# SCH_USB-Hub.net
KiCad netlist of a schematic drawn in EasyEDA
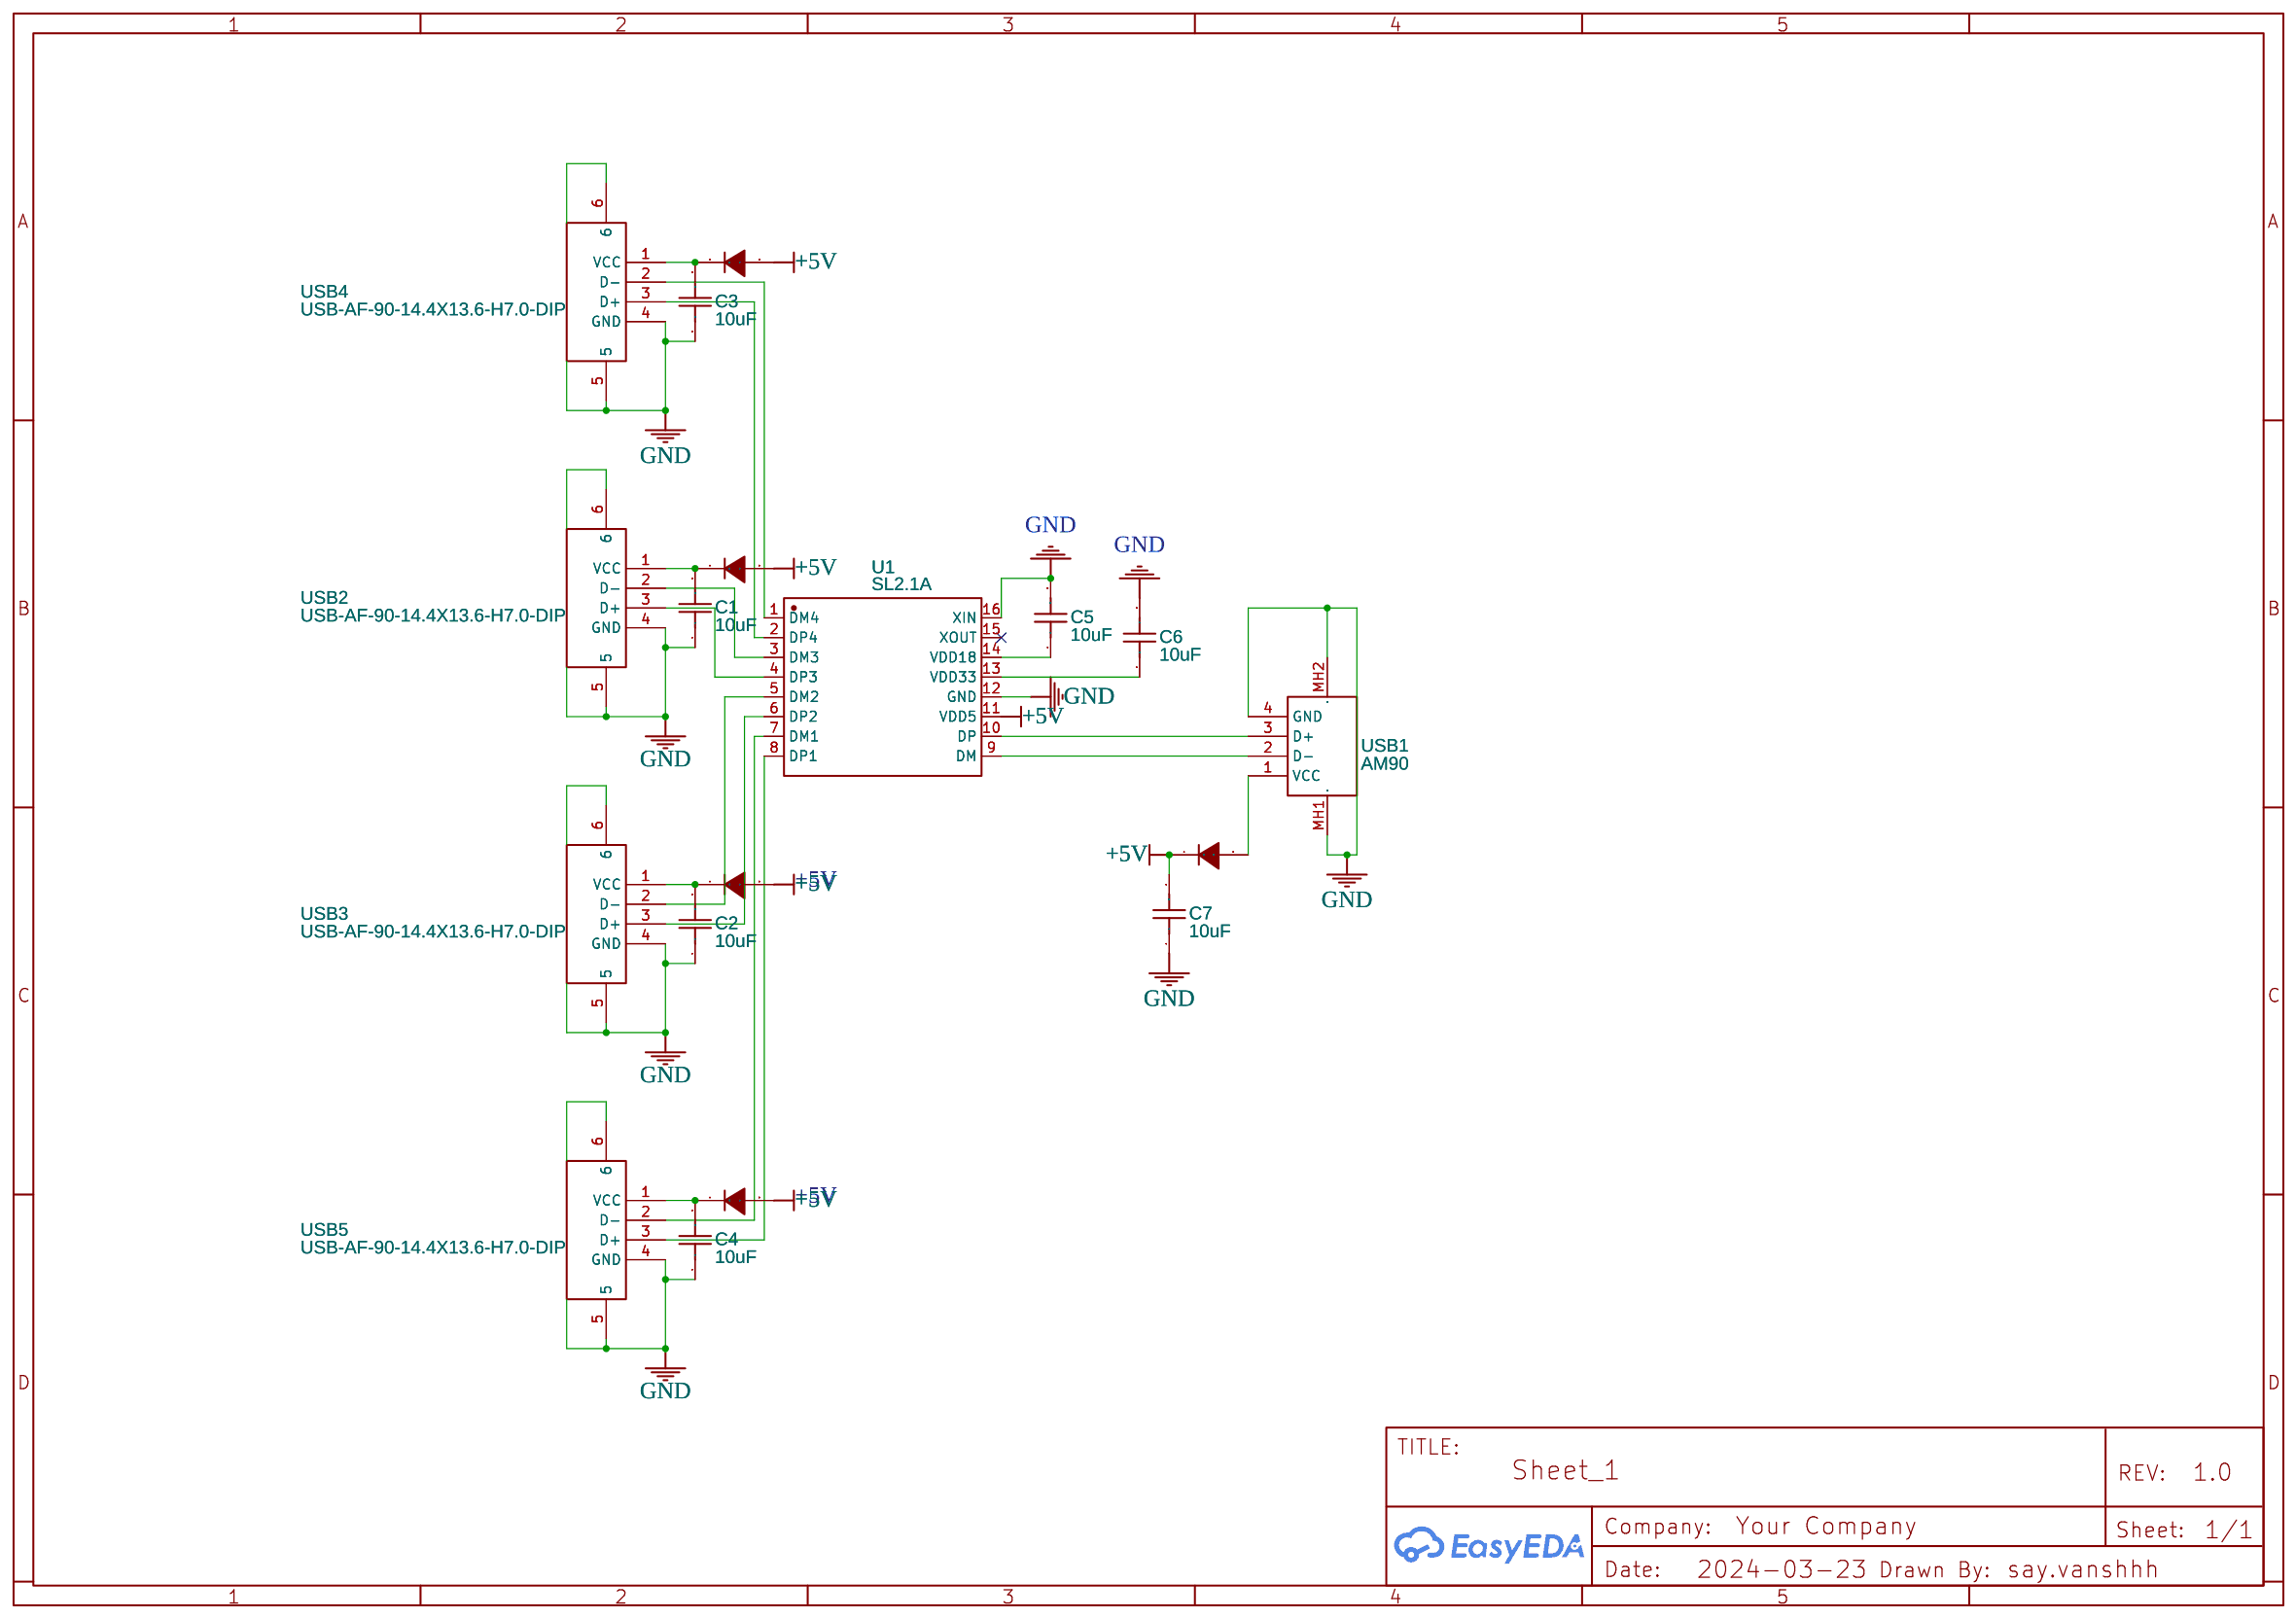
[diagram p0: schematic sheet]

(export (version "E")
  (design (tool "Eeschema 10.0.6"))
  (components
    (comp (ref "C1")
      (value "10uF")
      (fields
        (field (name "Manufacturer Part") "CL10A106KP8NNNC")
        (field (name "Manufacturer") "SAMSUNG(三星)")
      )
      (libsource (lib "") (part "CL10A106KP8NNNC"))
    )
    (comp (ref "C2")
      (value "10uF")
      (fields
        (field (name "Manufacturer Part") "CL10A106KP8NNNC")
        (field (name "Manufacturer") "SAMSUNG(三星)")
      )
      (libsource (lib "") (part "CL10A106KP8NNNC"))
    )
    (comp (ref "C3")
      (value "10uF")
      (fields
        (field (name "Manufacturer Part") "CL10A106KP8NNNC")
        (field (name "Manufacturer") "SAMSUNG(三星)")
      )
      (libsource (lib "") (part "CL10A106KP8NNNC"))
    )
    (comp (ref "C4")
      (value "10uF")
      (fields
        (field (name "Manufacturer Part") "CL10A106KP8NNNC")
        (field (name "Manufacturer") "SAMSUNG(三星)")
      )
      (libsource (lib "") (part "CL10A106KP8NNNC"))
    )
    (comp (ref "C5")
      (value "10uF")
      (fields
        (field (name "Manufacturer Part") "CL10A106KP8NNNC")
        (field (name "Manufacturer") "SAMSUNG(三星)")
      )
      (libsource (lib "") (part "CL10A106KP8NNNC"))
    )
    (comp (ref "C6")
      (value "10uF")
      (fields
        (field (name "Manufacturer Part") "CL10A106KP8NNNC")
        (field (name "Manufacturer") "SAMSUNG(三星)")
      )
      (libsource (lib "") (part "CL10A106KP8NNNC"))
    )
    (comp (ref "C7")
      (value "10uF")
      (fields
        (field (name "Manufacturer Part") "CL10A106KP8NNNC")
        (field (name "Manufacturer") "SAMSUNG(三星)")
      )
      (libsource (lib "") (part "CL10A106KP8NNNC"))
    )
    (comp (ref "D1")
      (value "NSR0320MW2T1G")
      (fields (field (name "Manufacturer") "onsemi(安森美)"))
      (libsource (lib "") (part "NSR0320MW2T1G"))
    )
    (comp (ref "D2")
      (value "NSR0320MW2T1G")
      (fields (field (name "Manufacturer") "onsemi(安森美)"))
      (libsource (lib "") (part "NSR0320MW2T1G"))
    )
    (comp (ref "D3")
      (value "NSR0320MW2T1G")
      (fields (field (name "Manufacturer") "onsemi(安森美)"))
      (libsource (lib "") (part "NSR0320MW2T1G"))
    )
    (comp (ref "D4")
      (value "NSR0320MW2T1G")
      (fields (field (name "Manufacturer") "onsemi(安森美)"))
      (libsource (lib "") (part "NSR0320MW2T1G"))
    )
    (comp (ref "D5")
      (value "NSR0320MW2T1G")
      (fields (field (name "Manufacturer") "onsemi(安森美)"))
      (libsource (lib "") (part "NSR0320MW2T1G"))
    )
    (comp (ref "U1")
      (value "SL2.1A")
      (fields (field (name "Manufacturer") "CoreChips(和芯润德)"))
      (libsource (lib "") (part "SL2.1A"))
    )
    (comp (ref "USB1")
      (value "AM90")
      (fields (field (name "Manufacturer") "SHOU HAN(首韩)"))
      (libsource (lib "") (part "AM90"))
    )
    (comp (ref "USB2")
      (value "USB-AF-90-14.4X13.6-H7.0-DIP")
      (fields (field (name "Manufacturer Part") "903-131A1011D10100") (field (name "Manufacturer") "精拓金"))
      (libsource (lib "") (part "USB-AF-90-14.4X13.6-H7.0-DIP"))
    )
    (comp (ref "USB3")
      (value "USB-AF-90-14.4X13.6-H7.0-DIP")
      (fields (field (name "Manufacturer Part") "903-131A1011D10100") (field (name "Manufacturer") "精拓金"))
      (libsource (lib "") (part "USB-AF-90-14.4X13.6-H7.0-DIP"))
    )
    (comp (ref "USB4")
      (value "USB-AF-90-14.4X13.6-H7.0-DIP")
      (fields (field (name "Manufacturer Part") "903-131A1011D10100") (field (name "Manufacturer") "精拓金"))
      (libsource (lib "") (part "USB-AF-90-14.4X13.6-H7.0-DIP"))
    )
    (comp (ref "USB5")
      (value "USB-AF-90-14.4X13.6-H7.0-DIP")
      (fields (field (name "Manufacturer Part") "903-131A1011D10100") (field (name "Manufacturer") "精拓金"))
      (libsource (lib "") (part "USB-AF-90-14.4X13.6-H7.0-DIP"))
    )
  )
  (nets
    (net (code "1") (name "+5V") (class "Default")
      (node (ref "C7") (pin "2") (pinfunction "2_2") (pintype "unspecified"))
      (node (ref "D1") (pin "2") (pinfunction "A_2") (pintype "unspecified"))
      (node (ref "D2") (pin "2") (pinfunction "A_2") (pintype "unspecified"))
      (node (ref "D3") (pin "2") (pinfunction "A_2") (pintype "unspecified"))
      (node (ref "D4") (pin "2") (pinfunction "A_2") (pintype "unspecified"))
      (node (ref "D5") (pin "1") (pinfunction "C_1") (pintype "unspecified"))
      (node (ref "U1") (pin "11") (pinfunction "VDD5_11") (pintype "unspecified"))
    )
    (net (code "2") (name "GND") (class "Default")
      (node (ref "C1") (pin "1") (pinfunction "1_1") (pintype "unspecified"))
      (node (ref "C2") (pin "1") (pinfunction "1_1") (pintype "unspecified"))
      (node (ref "C3") (pin "1") (pinfunction "1_1") (pintype "unspecified"))
      (node (ref "C4") (pin "1") (pinfunction "1_1") (pintype "unspecified"))
      (node (ref "C5") (pin "2") (pinfunction "2_2") (pintype "unspecified"))
      (node (ref "C6") (pin "2") (pinfunction "2_2") (pintype "unspecified"))
      (node (ref "C7") (pin "1") (pinfunction "1_1") (pintype "unspecified"))
      (node (ref "U1") (pin "12") (pinfunction "GND_12") (pintype "unspecified"))
      (node (ref "U1") (pin "16") (pinfunction "XIN_16") (pintype "unspecified"))
      (node (ref "USB1") (pin "4") (pinfunction "GND_4") (pintype "input"))
      (node (ref "USB1") (pin "MH1") (pinfunction "MH1_MH1") (pintype "unspecified"))
      (node (ref "USB1") (pin "MH2") (pinfunction "MH2_MH2") (pintype "unspecified"))
      (node (ref "USB2") (pin "4") (pinfunction "GND_4") (pintype "unspecified"))
      (node (ref "USB2") (pin "5") (pinfunction "5_5") (pintype "unspecified"))
      (node (ref "USB3") (pin "4") (pinfunction "GND_4") (pintype "unspecified"))
      (node (ref "USB3") (pin "5") (pinfunction "5_5") (pintype "unspecified"))
      (node (ref "USB4") (pin "4") (pinfunction "GND_4") (pintype "unspecified"))
      (node (ref "USB4") (pin "5") (pinfunction "5_5") (pintype "unspecified"))
      (node (ref "USB5") (pin "4") (pinfunction "GND_4") (pintype "unspecified"))
      (node (ref "USB5") (pin "5") (pinfunction "5_5") (pintype "unspecified"))
    )
    (net (code "3") (name "Net-(D1-C)") (class "Default")
      (node (ref "C1") (pin "2") (pinfunction "2_2") (pintype "unspecified"))
      (node (ref "D1") (pin "1") (pinfunction "C_1") (pintype "unspecified"))
      (node (ref "USB2") (pin "1") (pinfunction "VCC_1") (pintype "unspecified"))
    )
    (net (code "4") (name "Net-(D2-C)") (class "Default")
      (node (ref "C3") (pin "2") (pinfunction "2_2") (pintype "unspecified"))
      (node (ref "D2") (pin "1") (pinfunction "C_1") (pintype "unspecified"))
      (node (ref "USB4") (pin "1") (pinfunction "VCC_1") (pintype "unspecified"))
    )
    (net (code "5") (name "Net-(D3-C)") (class "Default")
      (node (ref "C2") (pin "2") (pinfunction "2_2") (pintype "unspecified"))
      (node (ref "D3") (pin "1") (pinfunction "C_1") (pintype "unspecified"))
      (node (ref "USB3") (pin "1") (pinfunction "VCC_1") (pintype "unspecified"))
    )
    (net (code "6") (name "Net-(D4-C)") (class "Default")
      (node (ref "C4") (pin "2") (pinfunction "2_2") (pintype "unspecified"))
      (node (ref "D4") (pin "1") (pinfunction "C_1") (pintype "unspecified"))
      (node (ref "USB5") (pin "1") (pinfunction "VCC_1") (pintype "unspecified"))
    )
    (net (code "7") (name "Net-(D5-A)") (class "Default")
      (node (ref "D5") (pin "2") (pinfunction "A_2") (pintype "unspecified"))
      (node (ref "USB1") (pin "1") (pinfunction "VCC_1") (pintype "input"))
    )
    (net (code "8") (name "Net-(U1-DM)") (class "Default")
      (node (ref "U1") (pin "9") (pinfunction "DM_9") (pintype "unspecified"))
      (node (ref "USB1") (pin "2") (pinfunction "D-_2") (pintype "input"))
    )
    (net (code "9") (name "Net-(U1-DM1)") (class "Default")
      (node (ref "U1") (pin "7") (pinfunction "DM1_7") (pintype "unspecified"))
      (node (ref "USB5") (pin "2") (pinfunction "D-_2") (pintype "unspecified"))
    )
    (net (code "10") (name "Net-(U1-DM2)") (class "Default")
      (node (ref "U1") (pin "5") (pinfunction "DM2_5") (pintype "unspecified"))
      (node (ref "USB3") (pin "2") (pinfunction "D-_2") (pintype "unspecified"))
    )
    (net (code "11") (name "Net-(U1-DM3)") (class "Default")
      (node (ref "U1") (pin "3") (pinfunction "DM3_3") (pintype "unspecified"))
      (node (ref "USB2") (pin "2") (pinfunction "D-_2") (pintype "unspecified"))
    )
    (net (code "12") (name "Net-(U1-DM4)") (class "Default")
      (node (ref "U1") (pin "1") (pinfunction "DM4_1") (pintype "unspecified"))
      (node (ref "USB4") (pin "2") (pinfunction "D-_2") (pintype "unspecified"))
    )
    (net (code "13") (name "Net-(U1-DP)") (class "Default")
      (node (ref "U1") (pin "10") (pinfunction "DP_10") (pintype "unspecified"))
      (node (ref "USB1") (pin "3") (pinfunction "D+_3") (pintype "input"))
    )
    (net (code "14") (name "Net-(U1-DP1)") (class "Default")
      (node (ref "U1") (pin "8") (pinfunction "DP1_8") (pintype "unspecified"))
      (node (ref "USB5") (pin "3") (pinfunction "D+_3") (pintype "unspecified"))
    )
    (net (code "15") (name "Net-(U1-DP2)") (class "Default")
      (node (ref "U1") (pin "6") (pinfunction "DP2_6") (pintype "unspecified"))
      (node (ref "USB3") (pin "3") (pinfunction "D+_3") (pintype "unspecified"))
    )
    (net (code "16") (name "Net-(U1-DP3)") (class "Default")
      (node (ref "U1") (pin "4") (pinfunction "DP3_4") (pintype "unspecified"))
      (node (ref "USB2") (pin "3") (pinfunction "D+_3") (pintype "unspecified"))
    )
    (net (code "17") (name "Net-(U1-DP4)") (class "Default")
      (node (ref "U1") (pin "2") (pinfunction "DP4_2") (pintype "unspecified"))
      (node (ref "USB4") (pin "3") (pinfunction "D+_3") (pintype "unspecified"))
    )
    (net (code "18") (name "Net-(U1-VDD18)") (class "Default")
      (node (ref "C5") (pin "1") (pinfunction "1_1") (pintype "unspecified"))
      (node (ref "U1") (pin "14") (pinfunction "VDD18_14") (pintype "unspecified"))
    )
    (net (code "19") (name "Net-(U1-VDD33)") (class "Default")
      (node (ref "C6") (pin "1") (pinfunction "1_1") (pintype "unspecified"))
      (node (ref "U1") (pin "13") (pinfunction "VDD33_13") (pintype "unspecified"))
    )
    (net (code "20") (name "unconnected-(U1-XOUT-Pad15)") (class "Default")
      (node (ref "U1") (pin "15") (pinfunction "XOUT_15") (pintype "unspecified+no_connect"))
    )
    (net (code "21") (name "unconnected-(USB2-Pad6)") (class "Default")
      (node (ref "USB2") (pin "6") (pinfunction "6_6") (pintype "unspecified"))
    )
    (net (code "22") (name "unconnected-(USB3-Pad6)") (class "Default")
      (node (ref "USB3") (pin "6") (pinfunction "6_6") (pintype "unspecified"))
    )
    (net (code "23") (name "unconnected-(USB4-Pad6)") (class "Default")
      (node (ref "USB4") (pin "6") (pinfunction "6_6") (pintype "unspecified"))
    )
    (net (code "24") (name "unconnected-(USB5-Pad6)") (class "Default")
      (node (ref "USB5") (pin "6") (pinfunction "6_6") (pintype "unspecified"))
    )
  )
)
